# Stepper_Motor_Driver_With_L297_-_l6201PS.net
KiCad netlist of a schematic drawn in Altium Designer
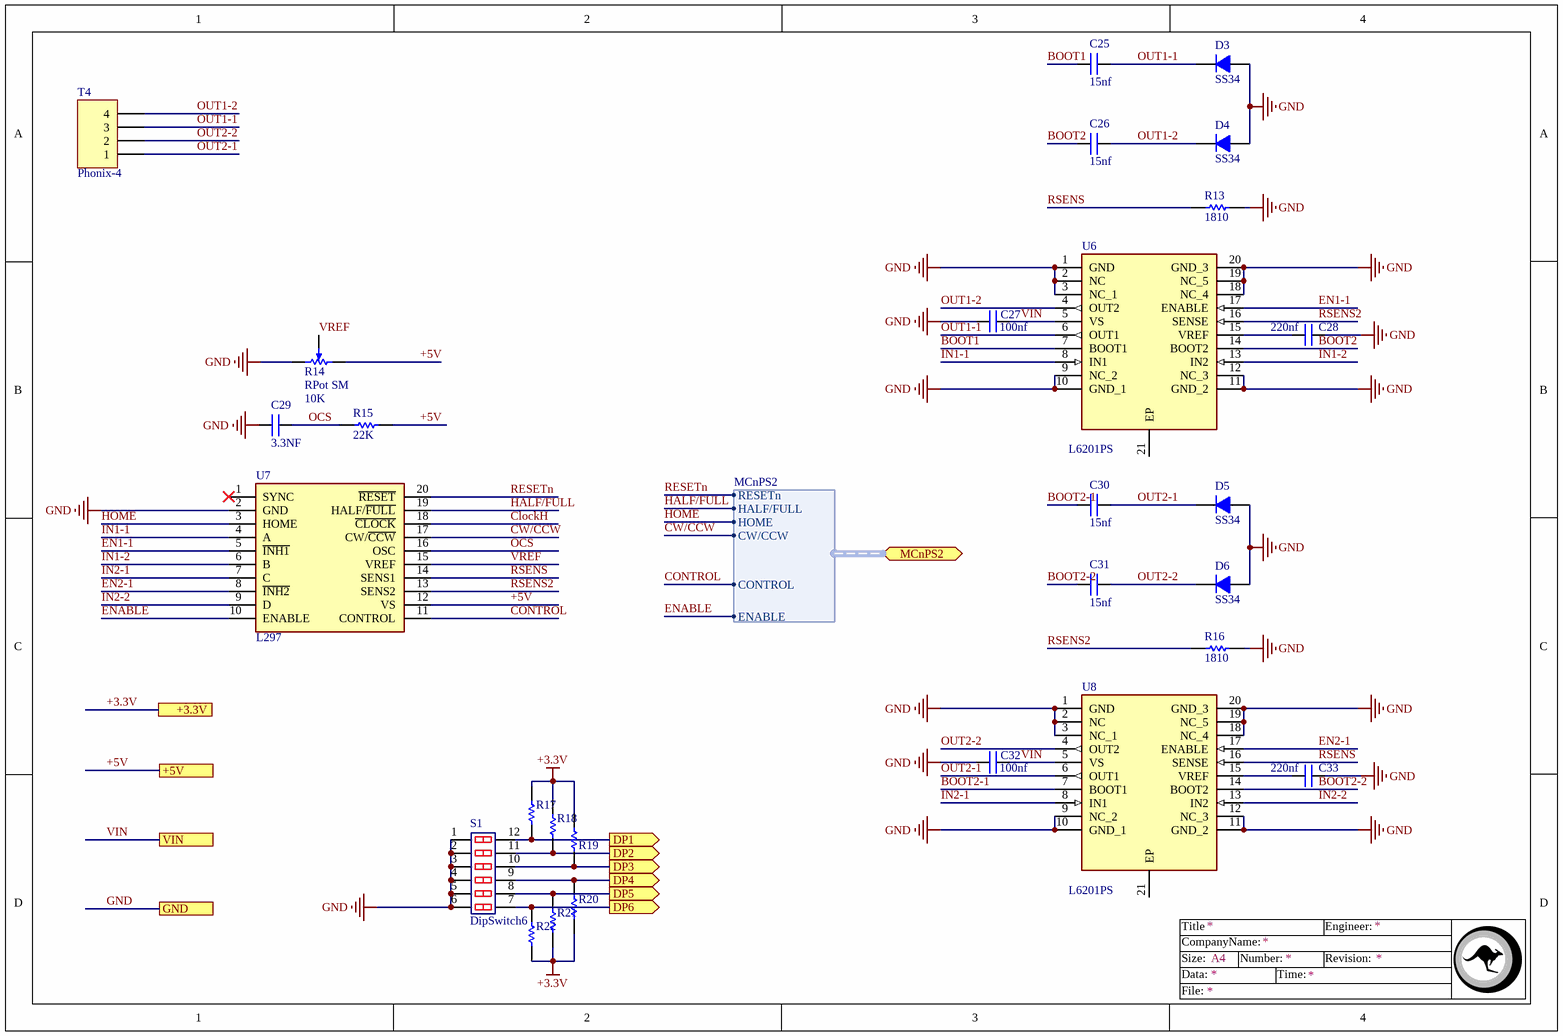
[diagram p0: Stepper Motor Driver With L297 - l6201PS.SchDoc]

(export (version "E")
  (design (tool "Eeschema 10.0.6"))
  (components
    (comp (ref "C25")
      (value "15nf")
      (footprint "Cap0805")
      (description "Surface mount Capacitor")
      (libsource (lib "PMLIB2020") (part "Cap"))
    )
    (comp (ref "C26")
      (value "15nf")
      (footprint "Cap0805")
      (description "Surface mount Capacitor")
      (libsource (lib "PMLIB2020") (part "Cap"))
    )
    (comp (ref "C27")
      (value "100nf")
      (footprint "Cap0805")
      (description "Surface mount Capacitor")
      (libsource (lib "PMLIB2020") (part "Cap"))
    )
    (comp (ref "C28")
      (value "220nf")
      (footprint "Cap0805")
      (description "Surface mount Capacitor")
      (libsource (lib "PMLIB2020") (part "Cap"))
    )
    (comp (ref "C29")
      (value "3.3NF")
      (footprint "Cap0805")
      (description "Surface mount Capacitor")
      (libsource (lib "PMLIB2020") (part "Cap"))
    )
    (comp (ref "C30")
      (value "15nf")
      (footprint "Cap0805")
      (description "Surface mount Capacitor")
      (libsource (lib "PMLIB2020") (part "Cap"))
    )
    (comp (ref "C31")
      (value "15nf")
      (footprint "Cap0805")
      (description "Surface mount Capacitor")
      (libsource (lib "PMLIB2020") (part "Cap"))
    )
    (comp (ref "C32")
      (value "100nf")
      (footprint "Cap0805")
      (description "Surface mount Capacitor")
      (libsource (lib "PMLIB2020") (part "Cap"))
    )
    (comp (ref "C33")
      (value "220nf")
      (footprint "Cap0805")
      (description "Surface mount Capacitor")
      (libsource (lib "PMLIB2020") (part "Cap"))
    )
    (comp (ref "D3")
      (value "SS34")
      (footprint "Diod-1A-SMD")
      (description "Diode")
      (libsource (lib "PMLIB2020") (part "Diode"))
    )
    (comp (ref "D4")
      (value "SS34")
      (footprint "Diod-1A-SMD")
      (description "Diode")
      (libsource (lib "PMLIB2020") (part "Diode"))
    )
    (comp (ref "D5")
      (value "SS34")
      (footprint "Diod-1A-SMD")
      (description "Diode")
      (libsource (lib "PMLIB2020") (part "Diode"))
    )
    (comp (ref "D6")
      (value "SS34")
      (footprint "Diod-1A-SMD")
      (description "Diode")
      (libsource (lib "PMLIB2020") (part "Diode"))
    )
    (comp (ref "R13")
      (value "1810")
      (footprint "RES1812")
      (description "Resistor")
      (libsource (lib "PMLIB2020") (part "Resistor"))
    )
    (comp (ref "R14")
      (value "RPot SM")
      (footprint "POT4MM-Small Pot")
      (description "Square Trimming Potentiometer")
      (fields (field (name "ALTIUM_VALUE") "10K") (field (name "PUBLISHER") "Altium Limited"))
      (libsource (lib "PMLIB2020") (part "RPot SM"))
    )
    (comp (ref "R15")
      (value "22K")
      (footprint "R0805")
      (description "Resistor")
      (libsource (lib "PMLIB2020") (part "Resistor"))
    )
    (comp (ref "R16")
      (value "1810")
      (footprint "RES1812")
      (description "Resistor")
      (libsource (lib "PMLIB2020") (part "Resistor"))
    )
    (comp (ref "R17") (value "Resistor") (footprint "R0805") (libsource (lib "PMLIB2020") (part "Resistor")))
    (comp (ref "R18") (value "Resistor") (footprint "R0805") (libsource (lib "PMLIB2020") (part "Resistor")))
    (comp (ref "R19") (value "Resistor") (footprint "R0805") (libsource (lib "PMLIB2020") (part "Resistor")))
    (comp (ref "R20") (value "Resistor") (footprint "R0805") (libsource (lib "PMLIB2020") (part "Resistor")))
    (comp (ref "R21") (value "Resistor") (footprint "R0805") (libsource (lib "PMLIB2020") (part "Resistor")))
    (comp (ref "R22") (value "Resistor") (footprint "R0805") (libsource (lib "PMLIB2020") (part "Resistor")))
    (comp (ref "S1")
      (value "DipSwitch6")
      (footprint "DIPSW6")
      (description "DipSwitch6pin")
      (libsource (lib "PMLIB2020") (part "DipSwitch6"))
    )
    (comp (ref "T4")
      (value "Phonix-4")
      (footprint "Phonix-4")
      (description "Connector")
      (libsource (lib "PMLIB2020") (part "Phonix-4"))
    )
    (comp (ref "U6")
      (value "L6201PS")
      (footprint "SOIC127P1420X360-21N")
      (description "High voltage, high current dual full-bridge driver")
      (libsource (lib "PMLIB2020") (part "L6201PS"))
    )
    (comp (ref "U7")
      (value "L297")
      (footprint "SOIC127P1032X265-20N")
      (description "Stepper Motor Controller IC")
      (libsource (lib "PMLIB2020") (part "L297"))
    )
    (comp (ref "U8")
      (value "L6201PS")
      (footprint "SOIC127P1420X360-21N")
      (description "High voltage, high current dual full-bridge driver")
      (libsource (lib "PMLIB2020") (part "L6201PS"))
    )
  )
  (nets
    (net (code "2") (name "+3.3V") (class "Default")
      (node (ref "R17") (pin "1") (pinfunction "1_1") (pintype "passive"))
      (node (ref "R18") (pin "1") (pinfunction "1_1") (pintype "passive"))
      (node (ref "R19") (pin "2") (pinfunction "2_2") (pintype "passive"))
      (node (ref "R20") (pin "2") (pinfunction "2_2") (pintype "passive"))
      (node (ref "R21") (pin "2") (pinfunction "2_2") (pintype "passive"))
      (node (ref "R22") (pin "2") (pinfunction "2_2") (pintype "passive"))
    )
    (net (code "3") (name "/+5V") (class "Default")
      (node (ref "R14") (pin "CCW") (pinfunction "-_CCW") (pintype "passive"))
      (node (ref "R15") (pin "1") (pinfunction "1_1") (pintype "passive"))
      (node (ref "U7") (pin "12") (pinfunction "VS_12") (pintype "passive"))
    )
    (net (code "4") (name "/BOOT1") (class "Default")
      (node (ref "C25") (pin "2") (pinfunction "2_2") (pintype "passive"))
      (node (ref "U6") (pin "7") (pinfunction "BOOT1_7") (pintype "passive"))
    )
    (net (code "5") (name "/BOOT2") (class "Default")
      (node (ref "C26") (pin "2") (pinfunction "2_2") (pintype "passive"))
      (node (ref "U6") (pin "14") (pinfunction "BOOT2_14") (pintype "passive"))
    )
    (net (code "6") (name "/BOOT2-1") (class "Default")
      (node (ref "C30") (pin "2") (pinfunction "2_2") (pintype "passive"))
      (node (ref "U8") (pin "7") (pinfunction "BOOT1_7") (pintype "passive"))
    )
    (net (code "7") (name "/BOOT2-2") (class "Default")
      (node (ref "C31") (pin "2") (pinfunction "2_2") (pintype "passive"))
      (node (ref "U8") (pin "14") (pinfunction "BOOT2_14") (pintype "passive"))
    )
    (net (code "8") (name "/CONTROL") (class "Default")
      (node (ref "U7") (pin "11") (pinfunction "CONTROL_11") (pintype "passive"))
    )
    (net (code "9") (name "/CW{slash}CCW") (class "Default")
      (node (ref "U7") (pin "17") (pinfunction "CW/~{CCW}_17") (pintype "passive"))
    )
    (net (code "10") (name "/ClockH") (class "Default")
      (node (ref "U7") (pin "18") (pinfunction "~{CLOCK}_18") (pintype "passive"))
    )
    (net (code "11") (name "/DP1") (class "Default")
      (node (ref "R17") (pin "2") (pinfunction "2_2") (pintype "passive"))
      (node (ref "S1") (pin "12") (pinfunction "12_12") (pintype "passive"))
    )
    (net (code "12") (name "/DP2") (class "Default")
      (node (ref "R18") (pin "2") (pinfunction "2_2") (pintype "passive"))
      (node (ref "S1") (pin "11") (pinfunction "11_11") (pintype "passive"))
    )
    (net (code "13") (name "/DP3") (class "Default")
      (node (ref "R19") (pin "1") (pinfunction "1_1") (pintype "passive"))
      (node (ref "S1") (pin "10") (pinfunction "10_10") (pintype "passive"))
    )
    (net (code "14") (name "/DP4") (class "Default")
      (node (ref "R20") (pin "1") (pinfunction "1_1") (pintype "passive"))
      (node (ref "S1") (pin "9") (pinfunction "9_9") (pintype "passive"))
    )
    (net (code "15") (name "/DP5") (class "Default")
      (node (ref "R21") (pin "1") (pinfunction "1_1") (pintype "passive"))
      (node (ref "S1") (pin "8") (pinfunction "8_8") (pintype "passive"))
    )
    (net (code "16") (name "/DP6") (class "Default")
      (node (ref "R22") (pin "1") (pinfunction "1_1") (pintype "passive"))
      (node (ref "S1") (pin "7") (pinfunction "7_7") (pintype "passive"))
    )
    (net (code "17") (name "/EN1-1") (class "Default")
      (node (ref "U6") (pin "17") (pinfunction "ENABLE_17") (pintype "input"))
      (node (ref "U7") (pin "5") (pinfunction "~{INH1}_5") (pintype "passive"))
    )
    (net (code "18") (name "/EN2-1") (class "Default")
      (node (ref "U7") (pin "8") (pinfunction "~{INH2}_8") (pintype "passive"))
      (node (ref "U8") (pin "17") (pinfunction "ENABLE_17") (pintype "input"))
    )
    (net (code "19") (name "/ENABLE") (class "Default")
      (node (ref "U7") (pin "10") (pinfunction "ENABLE_10") (pintype "passive"))
    )
    (net (code "20") (name "/HALF{slash}FULL") (class "Default")
      (node (ref "U7") (pin "19") (pinfunction "HALF/~{FULL}_19") (pintype "passive"))
    )
    (net (code "21") (name "/HOME") (class "Default")
      (node (ref "U7") (pin "3") (pinfunction "HOME_3") (pintype "passive"))
    )
    (net (code "22") (name "/IN1-1") (class "Default")
      (node (ref "U6") (pin "8") (pinfunction "IN1_8") (pintype "input"))
      (node (ref "U7") (pin "4") (pinfunction "A_4") (pintype "passive"))
    )
    (net (code "23") (name "/IN1-2") (class "Default")
      (node (ref "U6") (pin "13") (pinfunction "IN2_13") (pintype "input"))
      (node (ref "U7") (pin "6") (pinfunction "B_6") (pintype "passive"))
    )
    (net (code "24") (name "/IN2-1") (class "Default")
      (node (ref "U7") (pin "7") (pinfunction "C_7") (pintype "passive"))
      (node (ref "U8") (pin "8") (pinfunction "IN1_8") (pintype "input"))
    )
    (net (code "25") (name "/IN2-2") (class "Default")
      (node (ref "U7") (pin "9") (pinfunction "D_9") (pintype "passive"))
      (node (ref "U8") (pin "13") (pinfunction "IN2_13") (pintype "input"))
    )
    (net (code "26") (name "/OCS") (class "Default")
      (node (ref "C29") (pin "1") (pinfunction "1_1") (pintype "passive"))
      (node (ref "R15") (pin "2") (pinfunction "2_2") (pintype "passive"))
      (node (ref "U7") (pin "16") (pinfunction "OSC_16") (pintype "passive"))
    )
    (net (code "27") (name "/OUT1-1") (class "Default")
      (node (ref "C25") (pin "1") (pinfunction "1_1") (pintype "passive"))
      (node (ref "D3") (pin "K") (pinfunction "K_K") (pintype "passive"))
      (node (ref "T4") (pin "3") (pinfunction "3_3") (pintype "passive"))
      (node (ref "U6") (pin "6") (pinfunction "OUT1_6") (pintype "output"))
    )
    (net (code "28") (name "/OUT1-2") (class "Default")
      (node (ref "C26") (pin "1") (pinfunction "1_1") (pintype "passive"))
      (node (ref "D4") (pin "K") (pinfunction "K_K") (pintype "passive"))
      (node (ref "T4") (pin "4") (pinfunction "4_4") (pintype "passive"))
      (node (ref "U6") (pin "4") (pinfunction "OUT2_4") (pintype "output"))
    )
    (net (code "29") (name "/OUT2-1") (class "Default")
      (node (ref "C30") (pin "1") (pinfunction "1_1") (pintype "passive"))
      (node (ref "D5") (pin "K") (pinfunction "K_K") (pintype "passive"))
      (node (ref "T4") (pin "1") (pinfunction "1_1") (pintype "passive"))
      (node (ref "U8") (pin "6") (pinfunction "OUT1_6") (pintype "output"))
    )
    (net (code "30") (name "/OUT2-2") (class "Default")
      (node (ref "C31") (pin "1") (pinfunction "1_1") (pintype "passive"))
      (node (ref "D6") (pin "K") (pinfunction "K_K") (pintype "passive"))
      (node (ref "T4") (pin "2") (pinfunction "2_2") (pintype "passive"))
      (node (ref "U8") (pin "4") (pinfunction "OUT2_4") (pintype "output"))
    )
    (net (code "31") (name "/RESETn") (class "Default")
      (node (ref "U7") (pin "20") (pinfunction "~{RESET}_20") (pintype "passive"))
    )
    (net (code "32") (name "/RSENS") (class "Default")
      (node (ref "R13") (pin "2") (pinfunction "2_2") (pintype "passive"))
      (node (ref "U7") (pin "14") (pinfunction "SENS1_14") (pintype "passive"))
      (node (ref "U8") (pin "16") (pinfunction "SENSE_16") (pintype "input"))
    )
    (net (code "33") (name "/RSENS2") (class "Default")
      (node (ref "R16") (pin "2") (pinfunction "2_2") (pintype "passive"))
      (node (ref "U6") (pin "16") (pinfunction "SENSE_16") (pintype "input"))
      (node (ref "U7") (pin "13") (pinfunction "SENS2_13") (pintype "passive"))
    )
    (net (code "34") (name "/VIN") (class "Default")
      (node (ref "C27") (pin "2") (pinfunction "2_2") (pintype "passive"))
      (node (ref "C32") (pin "2") (pinfunction "2_2") (pintype "passive"))
      (node (ref "U6") (pin "5") (pinfunction "VS_5") (pintype "power_in"))
      (node (ref "U8") (pin "5") (pinfunction "VS_5") (pintype "power_in"))
    )
    (net (code "35") (name "/VREF") (class "Default")
      (node (ref "R14") (pin "W") (pinfunction "W_W") (pintype "passive"))
      (node (ref "U7") (pin "15") (pinfunction "VREF_15") (pintype "passive"))
    )
    (net (code "37") (name "GND") (class "Default")
      (node (ref "C27") (pin "1") (pinfunction "1_1") (pintype "passive"))
      (node (ref "C28") (pin "2") (pinfunction "2_2") (pintype "passive"))
      (node (ref "C29") (pin "2") (pinfunction "2_2") (pintype "passive"))
      (node (ref "C32") (pin "1") (pinfunction "1_1") (pintype "passive"))
      (node (ref "C33") (pin "2") (pinfunction "2_2") (pintype "passive"))
      (node (ref "D3") (pin "A") (pinfunction "A_A") (pintype "passive"))
      (node (ref "D4") (pin "A") (pinfunction "A_A") (pintype "passive"))
      (node (ref "D5") (pin "A") (pinfunction "A_A") (pintype "passive"))
      (node (ref "D6") (pin "A") (pinfunction "A_A") (pintype "passive"))
      (node (ref "R13") (pin "1") (pinfunction "1_1") (pintype "passive"))
      (node (ref "R14") (pin "CW") (pinfunction "+_CW") (pintype "passive"))
      (node (ref "R16") (pin "1") (pinfunction "1_1") (pintype "passive"))
      (node (ref "S1") (pin "1") (pinfunction "1_1") (pintype "passive"))
      (node (ref "S1") (pin "2") (pinfunction "2_2") (pintype "passive"))
      (node (ref "S1") (pin "3") (pinfunction "3_3") (pintype "passive"))
      (node (ref "S1") (pin "4") (pinfunction "4_4") (pintype "passive"))
      (node (ref "S1") (pin "5") (pinfunction "5_5") (pintype "passive"))
      (node (ref "S1") (pin "6") (pinfunction "6_6") (pintype "passive"))
      (node (ref "U6") (pin "1") (pinfunction "GND_1") (pintype "power_in"))
      (node (ref "U6") (pin "10") (pinfunction "GND_1_10") (pintype "power_in"))
      (node (ref "U6") (pin "11") (pinfunction "GND_2_11") (pintype "power_in"))
      (node (ref "U6") (pin "12") (pinfunction "NC_3_12") (pintype "passive"))
      (node (ref "U6") (pin "18") (pinfunction "NC_4_18") (pintype "passive"))
      (node (ref "U6") (pin "19") (pinfunction "NC_5_19") (pintype "passive"))
      (node (ref "U6") (pin "2") (pinfunction "NC_2") (pintype "passive"))
      (node (ref "U6") (pin "20") (pinfunction "GND_3_20") (pintype "power_in"))
      (node (ref "U6") (pin "3") (pinfunction "NC_1_3") (pintype "passive"))
      (node (ref "U6") (pin "9") (pinfunction "NC_2_9") (pintype "passive"))
      (node (ref "U7") (pin "2") (pinfunction "GND_2") (pintype "passive"))
      (node (ref "U8") (pin "1") (pinfunction "GND_1") (pintype "power_in"))
      (node (ref "U8") (pin "10") (pinfunction "GND_1_10") (pintype "power_in"))
      (node (ref "U8") (pin "11") (pinfunction "GND_2_11") (pintype "power_in"))
      (node (ref "U8") (pin "12") (pinfunction "NC_3_12") (pintype "passive"))
      (node (ref "U8") (pin "18") (pinfunction "NC_4_18") (pintype "passive"))
      (node (ref "U8") (pin "19") (pinfunction "NC_5_19") (pintype "passive"))
      (node (ref "U8") (pin "2") (pinfunction "NC_2") (pintype "passive"))
      (node (ref "U8") (pin "20") (pinfunction "GND_3_20") (pintype "power_in"))
      (node (ref "U8") (pin "3") (pinfunction "NC_1_3") (pintype "passive"))
      (node (ref "U8") (pin "9") (pinfunction "NC_2_9") (pintype "passive"))
    )
    (net (code "38") (name "Net-(U6-VREF)") (class "Default")
      (node (ref "C28") (pin "1") (pinfunction "1_1") (pintype "passive"))
      (node (ref "U6") (pin "15") (pinfunction "VREF_15") (pintype "power_in"))
    )
    (net (code "39") (name "Net-(U8-VREF)") (class "Default")
      (node (ref "C33") (pin "1") (pinfunction "1_1") (pintype "passive"))
      (node (ref "U8") (pin "15") (pinfunction "VREF_15") (pintype "power_in"))
    )
    (net (code "40") (name "unconnected-(U6-EP-Pad21)") (class "Default")
      (node (ref "U6") (pin "21") (pinfunction "EP_21") (pintype "passive"))
    )
    (net (code "41") (name "unconnected-(U7-SYNC-Pad1)") (class "Default")
      (node (ref "U7") (pin "1") (pinfunction "SYNC_1") (pintype "passive+no_connect"))
    )
    (net (code "42") (name "unconnected-(U8-EP-Pad21)") (class "Default")
      (node (ref "U8") (pin "21") (pinfunction "EP_21") (pintype "passive"))
    )
  )
)
